# Ham-Dip-V2-002.net
KiCad netlist of a schematic drawn in EAGLE
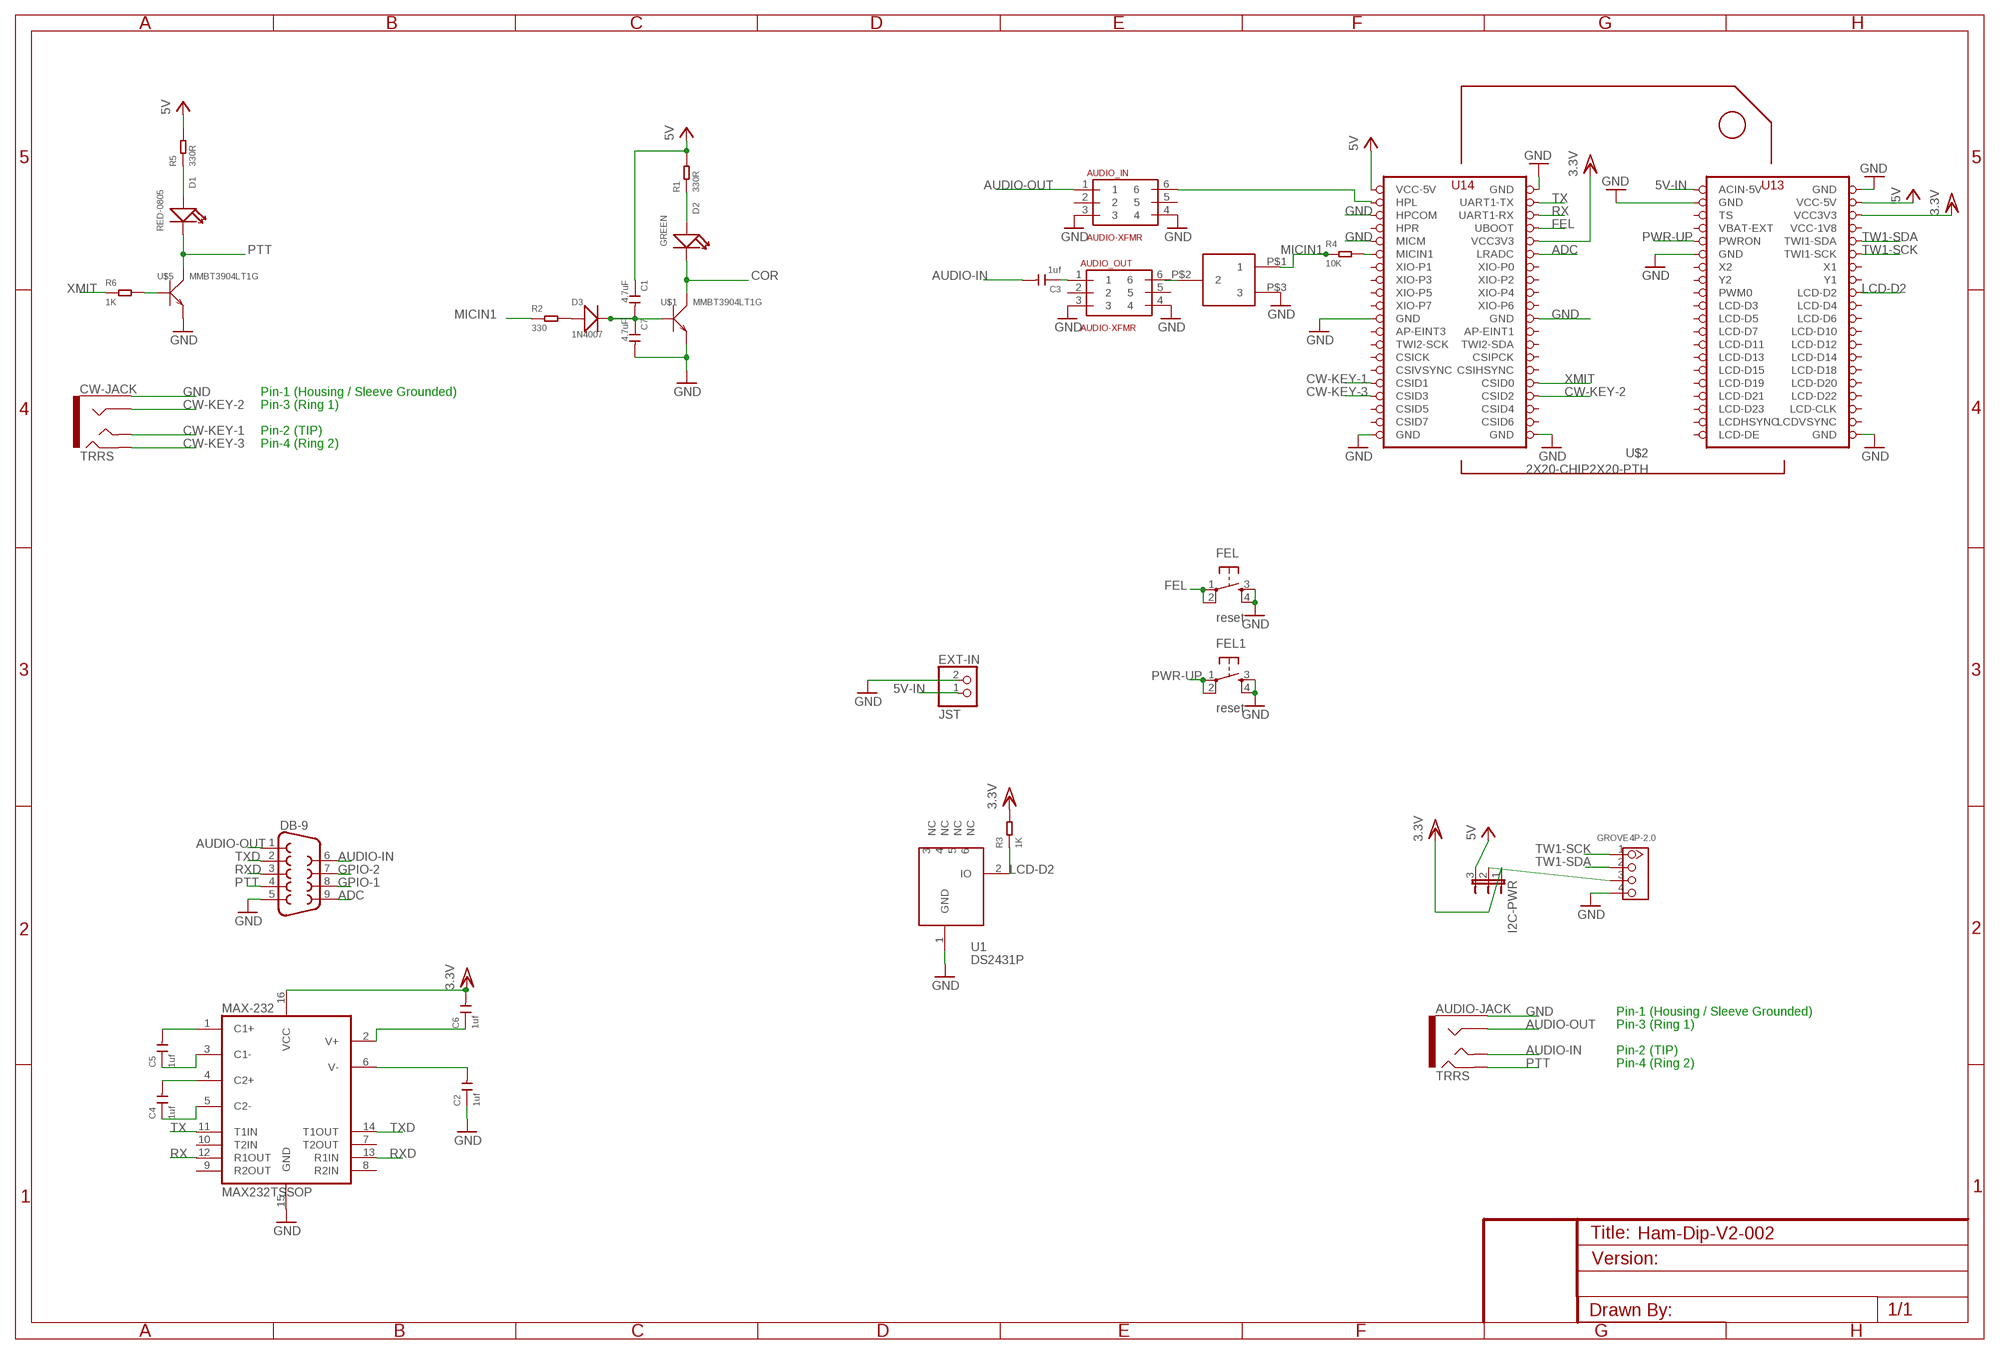
[diagram p0: schematic, sheet 1]

(export (version "E")
  (design (tool "Eeschema 10.0.6"))
  (components
    (comp (ref "AUDIO-JACK")
      (value "TRRS")
      (footprint "eagle-import:AUDIO-JACK-TRRS-SMD")
      (libsource (lib "eagle-import") (part "AUDIO-JACK3"))
    )
    (comp (ref "AUDIO_IN")
      (value "AUDIO-XFMR")
      (footprint "eagle-import:SM-LP-5001")
      (libsource (lib "eagle-import") (part "SM-LP-5001"))
    )
    (comp (ref "AUDIO_OUT")
      (value "AUDIO-XFMR")
      (footprint "eagle-import:SM-LP-5001")
      (libsource (lib "eagle-import") (part "SM-LP-5001"))
    )
    (comp (ref "C1")
      (value "4.7uF")
      (footprint "eagle-import:C0805")
      (fields (field (name "MPN") "CC0805KKX7R8BB105"))
      (libsource (lib "eagle-import") (part "CERAMIC-1UF-25V-10%-X7R(0805)"))
    )
    (comp (ref "C2")
      (value "1uf")
      (footprint "eagle-import:C0805")
      (fields (field (name "MPN") "CC0805KKX7R8BB105"))
      (libsource (lib "eagle-import") (part "CERAMIC-1UF-25V-10%-X7R(0805)"))
    )
    (comp (ref "C3")
      (value "1uf")
      (footprint "eagle-import:C0805")
      (fields (field (name "MPN") "CC0805KKX7R8BB105"))
      (libsource (lib "eagle-import") (part "CERAMIC-1UF-25V-10%-X7R(0805)"))
    )
    (comp (ref "C4")
      (value "1uf")
      (footprint "eagle-import:C0805")
      (fields (field (name "MPN") "CC0805KKX7R8BB105"))
      (libsource (lib "eagle-import") (part "CERAMIC-1UF-25V-10%-X7R(0805)"))
    )
    (comp (ref "C5")
      (value "1uf")
      (footprint "eagle-import:C0805")
      (fields (field (name "MPN") "CC0805KKX7R8BB105"))
      (libsource (lib "eagle-import") (part "CERAMIC-1UF-25V-10%-X7R(0805)"))
    )
    (comp (ref "C6")
      (value "1uf")
      (footprint "eagle-import:C0805")
      (fields (field (name "MPN") "CC0805KKX7R8BB105"))
      (libsource (lib "eagle-import") (part "CERAMIC-1UF-25V-10%-X7R(0805)"))
    )
    (comp (ref "C7")
      (value "4.7uF")
      (footprint "eagle-import:C0805")
      (fields (field (name "MPN") "CC0805KKX7R8BB105"))
      (libsource (lib "eagle-import") (part "CERAMIC-1UF-25V-10%-X7R(0805)"))
    )
    (comp (ref "CW-JACK")
      (value "TRRS")
      (footprint "eagle-import:AUDIO-JACK-TRRS-SMD")
      (libsource (lib "eagle-import") (part "AUDIO-JACK3"))
    )
    (comp (ref "D1")
      (value "RED-0805")
      (footprint "eagle-import:LED-0805")
      (fields (field (name "MPN") "17-215SURC/S530-A2/TR8"))
      (libsource (lib "eagle-import") (part "SMD-LED-CLEAR-RED(0805)"))
    )
    (comp (ref "D2")
      (value "GREEN")
      (footprint "eagle-import:LED-0805")
      (fields (field (name "MPN") "17-215SURC/S530-A2/TR8"))
      (libsource (lib "eagle-import") (part "SMD-LED-CLEAR-RED(0805)"))
    )
    (comp (ref "D3")
      (value "1N4007")
      (footprint "eagle-import:DO-214AC")
      (libsource (lib "eagle-import") (part "DIODE-GEN-PURPOSE-1KV-1A(DO-214AC)"))
    )
    (comp (ref "DB-9")
      (value "DB9FEMALE")
      (footprint "eagle-import:DB9")
      (libsource (lib "eagle-import") (part "DB9FEMALE"))
    )
    (comp (ref "EXT-IN")
      (value "JST")
      (footprint "eagle-import:JST-PH-2-THM")
      (libsource (lib "eagle-import") (part "JST_2PIN-THM"))
    )
    (comp (ref "FEL")
      (value "reset")
      (footprint "eagle-import:TACTILE_SWITCH_SMD")
      (libsource (lib "eagle-import") (part "TAC_SWITCHSMD"))
    )
    (comp (ref "FEL1")
      (value "reset")
      (footprint "eagle-import:TACTILE_SWITCH_SMD")
      (libsource (lib "eagle-import") (part "TAC_SWITCHSMD"))
    )
    (comp (ref "GROVE")
      (value "4P-2.0")
      (footprint "eagle-import:HW4-2.0")
      (libsource (lib "eagle-import") (part "GROVE-CONNECTOR-DIP(4P-2.0)"))
    )
    (comp (ref "I2C-PWR")
      (value "JP2E")
      (footprint "eagle-import:JP2")
      (libsource (lib "eagle-import") (part "JP2E"))
    )
    (comp (ref "MAX-232")
      (value "MAX232TSSOP")
      (footprint "eagle-import:TSSOP16")
      (libsource (lib "eagle-import") (part "MAX232TSSOP"))
    )
    (comp (ref "R1")
      (value "330R")
      (footprint "eagle-import:R0805")
      (fields (field (name "MPN") "RC0805JR-07220RL"))
      (libsource (lib "eagle-import") (part "SMD-RES-220R-5%-1/8W(0805)"))
    )
    (comp (ref "R2")
      (value "330")
      (footprint "eagle-import:R0805")
      (fields (field (name "MPN") "RC0805JR-07220RL"))
      (libsource (lib "eagle-import") (part "SMD-RES-220R-5%-1/8W(0805)"))
    )
    (comp (ref "R3")
      (value "1K")
      (footprint "eagle-import:R0805")
      (fields (field (name "MPN") "RC0805JR-07220RL"))
      (libsource (lib "eagle-import") (part "SMD-RES-220R-5%-1/8W(0805)"))
    )
    (comp (ref "R4")
      (value "10K")
      (footprint "eagle-import:R0805")
      (fields (field (name "MPN") "RC0805FR-0710KL"))
      (libsource (lib "eagle-import") (part "SMD-RES-10K-1%-1/8W(0805)"))
    )
    (comp (ref "R5")
      (value "330R")
      (footprint "eagle-import:R0805")
      (fields (field (name "MPN") "RC0805JR-07220RL"))
      (libsource (lib "eagle-import") (part "SMD-RES-220R-5%-1/8W(0805)"))
    )
    (comp (ref "R6")
      (value "1K")
      (footprint "eagle-import:R0805")
      (fields (field (name "MPN") "RC0805JR-07220RL"))
      (libsource (lib "eagle-import") (part "SMD-RES-220R-5%-1/8W(0805)"))
    )
    (comp (ref "U$1")
      (value "MMBT3904LT1G")
      (footprint "eagle-import:SOT-23")
      (libsource (lib "eagle-import") (part "SMD-TRANSISTORS-NPN-40V-200MA-MMBT3904LT1G(SOT-23)"))
    )
    (comp (ref "U$2")
      (value "2X20-CHIP2X20-PTH")
      (footprint "eagle-import:2X20CHIP-TH")
      (fields (field (name "VENDOR_PART_NUMBER") "AWHW40-G-SMD-R (single)"))
      (libsource (lib "eagle-import") (part "2X20-CHIP2X20-PTH-CHIP_A"))
    )
    (comp (ref "U$3")
      (value "TC33X")
      (footprint "eagle-import:TC33X")
      (libsource (lib "eagle-import") (part "TC33X"))
    )
    (comp (ref "U$5")
      (value "MMBT3904LT1G")
      (footprint "eagle-import:SOT-23")
      (libsource (lib "eagle-import") (part "SMD-TRANSISTORS-NPN-40V-200MA-MMBT3904LT1G(SOT-23)"))
    )
    (comp (ref "U1")
      (value "DS2431P")
      (footprint "eagle-import:TSOC6")
      (fields (field (name "MFG") "DIGIKEY") (field (name "VENDOR_PART_NUMBER") "DS2431P+T&R"))
      (libsource (lib "eagle-import") (part "DS2431P"))
    )
  )
  (nets
    (net (code "1") (name "/5V-IN") (class "Default")
      (node (ref "EXT-IN") (pin "1") (pinfunction "2_1") (pintype "passive"))
      (node (ref "U$2") (pin "CHG-IN") (pinfunction "ACIN-5V_CHG-IN") (pintype "passive"))
    )
    (net (code "2") (name "/ADC") (class "Default")
      (node (ref "DB-9") (pin "9") (pinfunction "9_9") (pintype "passive"))
      (node (ref "U$2") (pin "LRADC") (pinfunction "LRADC_LRADC") (pintype "passive"))
    )
    (net (code "3") (name "/AUDIO-IN") (class "Default")
      (node (ref "AUDIO-JACK") (pin "TIP") (pinfunction "TIP_TIP") (pintype "bidirectional"))
      (node (ref "C3") (pin "2") (pinfunction "2_2") (pintype "passive"))
      (node (ref "DB-9") (pin "6") (pinfunction "6_6") (pintype "passive"))
    )
    (net (code "4") (name "/AUDIO-OUT") (class "Default")
      (node (ref "AUDIO-JACK") (pin "RING1") (pinfunction "RING1_RING1") (pintype "bidirectional"))
      (node (ref "AUDIO_IN") (pin "1") (pinfunction "1_1") (pintype "bidirectional"))
      (node (ref "DB-9") (pin "1") (pinfunction "1_1") (pintype "passive"))
    )
    (net (code "5") (name "/COR") (class "Default")
      (node (ref "D2") (pin "-") (pinfunction "-_-") (pintype "passive"))
      (node (ref "U$1") (pin "3") (pinfunction "C_3") (pintype "passive"))
    )
    (net (code "6") (name "/CW-KEY-1") (class "Default")
      (node (ref "CW-JACK") (pin "TIP") (pinfunction "TIP_TIP") (pintype "bidirectional"))
      (node (ref "U$2") (pin "CSID1") (pinfunction "CSID1_CSID1") (pintype "passive"))
    )
    (net (code "7") (name "/CW-KEY-2") (class "Default")
      (node (ref "CW-JACK") (pin "RING1") (pinfunction "RING1_RING1") (pintype "bidirectional"))
      (node (ref "U$2") (pin "CSID2") (pinfunction "CSID2_CSID2") (pintype "passive"))
    )
    (net (code "8") (name "/CW-KEY-3") (class "Default")
      (node (ref "CW-JACK") (pin "RING2") (pinfunction "RING2_RING2") (pintype "bidirectional"))
      (node (ref "U$2") (pin "CSID3") (pinfunction "CSID3_CSID3") (pintype "passive"))
    )
    (net (code "9") (name "/FEL") (class "Default")
      (node (ref "FEL") (pin "1") (pinfunction "1_1") (pintype "passive"))
      (node (ref "FEL") (pin "2") (pinfunction "2_2") (pintype "passive"))
      (node (ref "U$2") (pin "FEL") (pinfunction "UBOOT_FEL") (pintype "passive"))
    )
    (net (code "10") (name "/GPIO-1") (class "Default")
      (node (ref "DB-9") (pin "8") (pinfunction "8_8") (pintype "passive"))
    )
    (net (code "11") (name "/GPIO-2") (class "Default")
      (node (ref "DB-9") (pin "7") (pinfunction "7_7") (pintype "passive"))
    )
    (net (code "12") (name "/LCD-D2") (class "Default")
      (node (ref "R3") (pin "1") (pinfunction "1_1") (pintype "passive"))
      (node (ref "U$2") (pin "LCD-D2") (pinfunction "LCD-D2_LCD-D2") (pintype "passive"))
      (node (ref "U1") (pin "2") (pinfunction "IO_2") (pintype "bidirectional"))
    )
    (net (code "13") (name "/MICIN1") (class "Default")
      (node (ref "R2") (pin "1") (pinfunction "1_1") (pintype "passive"))
      (node (ref "R4") (pin "2") (pinfunction "2_2") (pintype "passive"))
      (node (ref "U$2") (pin "MICIN1") (pinfunction "MICIN1_MICIN1") (pintype "passive"))
    )
    (net (code "14") (name "/PTT") (class "Default")
      (node (ref "AUDIO-JACK") (pin "RING2") (pinfunction "RING2_RING2") (pintype "bidirectional"))
      (node (ref "D1") (pin "-") (pinfunction "-_-") (pintype "passive"))
      (node (ref "DB-9") (pin "4") (pinfunction "4_4") (pintype "passive"))
      (node (ref "U$5") (pin "3") (pinfunction "C_3") (pintype "passive"))
    )
    (net (code "15") (name "/PWR-UP") (class "Default")
      (node (ref "FEL1") (pin "1") (pinfunction "1_1") (pintype "passive"))
      (node (ref "FEL1") (pin "2") (pinfunction "2_2") (pintype "passive"))
      (node (ref "U$2") (pin "PWRON") (pinfunction "PWRON_PWRON") (pintype "passive"))
    )
    (net (code "16") (name "/RX") (class "Default")
      (node (ref "MAX-232") (pin "12") (pinfunction "R1OUT_12") (pintype "output"))
      (node (ref "U$2") (pin "UART1-RX") (pinfunction "UART1-RX_UART1-RX") (pintype "passive"))
    )
    (net (code "17") (name "/RXD") (class "Default")
      (node (ref "DB-9") (pin "3") (pinfunction "3_3") (pintype "passive"))
      (node (ref "MAX-232") (pin "13") (pinfunction "R1IN_13") (pintype "input"))
    )
    (net (code "18") (name "/TW1-SCK") (class "Default")
      (node (ref "GROVE") (pin "1") (pinfunction "1_1") (pintype "bidirectional"))
      (node (ref "U$2") (pin "TWI1-SCK") (pinfunction "TWI1-SCK_TWI1-SCK") (pintype "passive"))
    )
    (net (code "19") (name "/TW1-SDA") (class "Default")
      (node (ref "GROVE") (pin "2") (pinfunction "2_2") (pintype "bidirectional"))
      (node (ref "U$2") (pin "TWI1-SDA") (pinfunction "TWI1-SDA_TWI1-SDA") (pintype "passive"))
    )
    (net (code "20") (name "/TX") (class "Default")
      (node (ref "MAX-232") (pin "11") (pinfunction "T1IN_11") (pintype "input"))
      (node (ref "U$2") (pin "UART1-TX") (pinfunction "UART1-TX_UART1-TX") (pintype "passive"))
    )
    (net (code "21") (name "/TXD") (class "Default")
      (node (ref "DB-9") (pin "2") (pinfunction "2_2") (pintype "passive"))
      (node (ref "MAX-232") (pin "14") (pinfunction "T1OUT_14") (pintype "output"))
    )
    (net (code "22") (name "/VCC-1V8") (class "Default")
      (node (ref "U$2") (pin "VCC1V8") (pinfunction "VCC-1V8_VCC1V8") (pintype "power_in"))
    )
    (net (code "23") (name "/XMIT") (class "Default")
      (node (ref "R6") (pin "1") (pinfunction "1_1") (pintype "passive"))
      (node (ref "U$2") (pin "CSID0") (pinfunction "CSID0_CSID0") (pintype "passive"))
    )
    (net (code "24") (name "3.3V") (class "Default")
      (node (ref "C6") (pin "2") (pinfunction "2_2") (pintype "passive"))
      (node (ref "I2C-PWR") (pin "1") (pinfunction "1_1") (pintype "passive"))
      (node (ref "MAX-232") (pin "16") (pinfunction "VCC_16") (pintype "bidirectional"))
      (node (ref "R3") (pin "2") (pinfunction "2_2") (pintype "passive"))
      (node (ref "U$2") (pin "VCC3V3") (pinfunction "VCC3V3_VCC3V3") (pintype "power_in"))
      (node (ref "U$2") (pin "VCC3V3@1") (pinfunction "VCC3V3_VCC3V3@1") (pintype "power_in"))
    )
    (net (code "25") (name "5V") (class "Default")
      (node (ref "C1") (pin "1") (pinfunction "1_1") (pintype "passive"))
      (node (ref "I2C-PWR") (pin "3") (pinfunction "3_3") (pintype "passive"))
      (node (ref "R1") (pin "2") (pinfunction "2_2") (pintype "passive"))
      (node (ref "R5") (pin "2") (pinfunction "2_2") (pintype "passive"))
      (node (ref "U$2") (pin "VCC5V@0") (pinfunction "VCC-5V_VCC5V@0") (pintype "power_in"))
      (node (ref "U$2") (pin "VCC5V@1") (pinfunction "VCC-5V_VCC5V@1") (pintype "power_in"))
    )
    (net (code "26") (name "GND") (class "Default")
      (node (ref "AUDIO-JACK") (pin "EARTH") (pinfunction "EARTH_EARTH") (pintype "bidirectional"))
      (node (ref "AUDIO_IN") (pin "3") (pinfunction "3_3") (pintype "bidirectional"))
      (node (ref "AUDIO_IN") (pin "4") (pinfunction "4_4") (pintype "bidirectional"))
      (node (ref "AUDIO_OUT") (pin "3") (pinfunction "3_3") (pintype "bidirectional"))
      (node (ref "AUDIO_OUT") (pin "4") (pinfunction "4_4") (pintype "bidirectional"))
      (node (ref "C2") (pin "1") (pinfunction "1_1") (pintype "passive"))
      (node (ref "C7") (pin "2") (pinfunction "2_2") (pintype "passive"))
      (node (ref "CW-JACK") (pin "EARTH") (pinfunction "EARTH_EARTH") (pintype "bidirectional"))
      (node (ref "DB-9") (pin "5") (pinfunction "5_5") (pintype "passive"))
      (node (ref "EXT-IN") (pin "2") (pinfunction "1_2") (pintype "passive"))
      (node (ref "FEL") (pin "3") (pinfunction "3_3") (pintype "passive"))
      (node (ref "FEL") (pin "4") (pinfunction "4_4") (pintype "passive"))
      (node (ref "FEL1") (pin "3") (pinfunction "3_3") (pintype "passive"))
      (node (ref "FEL1") (pin "4") (pinfunction "4_4") (pintype "passive"))
      (node (ref "GROVE") (pin "4") (pinfunction "4_4") (pintype "bidirectional"))
      (node (ref "MAX-232") (pin "15") (pinfunction "GND_15") (pintype "bidirectional"))
      (node (ref "U$1") (pin "2") (pinfunction "E_2") (pintype "passive"))
      (node (ref "U$2") (pin "GND@1") (pinfunction "GND_GND@1") (pintype "power_in"))
      (node (ref "U$2") (pin "GND@10") (pinfunction "GND_GND@10") (pintype "power_in"))
      (node (ref "U$2") (pin "GND@2") (pinfunction "GND_GND@2") (pintype "power_in"))
      (node (ref "U$2") (pin "GND@3") (pinfunction "GND_GND@3") (pintype "power_in"))
      (node (ref "U$2") (pin "GND@4") (pinfunction "GND_GND@4") (pintype "power_in"))
      (node (ref "U$2") (pin "GND@5") (pinfunction "GND_GND@5") (pintype "power_in"))
      (node (ref "U$2") (pin "GND@6") (pinfunction "GND_GND@6") (pintype "power_in"))
      (node (ref "U$2") (pin "GND@7") (pinfunction "GND_GND@7") (pintype "power_in"))
      (node (ref "U$2") (pin "GND@8") (pinfunction "GND_GND@8") (pintype "power_in"))
      (node (ref "U$2") (pin "HPCOM") (pinfunction "HPCOM_HPCOM") (pintype "passive"))
      (node (ref "U$2") (pin "MICM") (pinfunction "MICM_MICM") (pintype "passive"))
      (node (ref "U$3") (pin "P$3") (pinfunction "3_P$3") (pintype "bidirectional"))
      (node (ref "U$5") (pin "2") (pinfunction "E_2") (pintype "passive"))
      (node (ref "U1") (pin "1") (pinfunction "GND_1") (pintype "bidirectional"))
    )
    (net (code "27") (name "Net-(AUDIO_IN-Pad6)") (class "Default")
      (node (ref "AUDIO_IN") (pin "6") (pinfunction "6_6") (pintype "bidirectional"))
      (node (ref "U$2") (pin "HPL") (pinfunction "HPL_HPL") (pintype "passive"))
    )
    (net (code "28") (name "Net-(AUDIO_OUT-Pad1)") (class "Default")
      (node (ref "AUDIO_OUT") (pin "1") (pinfunction "1_1") (pintype "bidirectional"))
      (node (ref "C3") (pin "1") (pinfunction "1_1") (pintype "passive"))
    )
    (net (code "29") (name "Net-(D1-Pad+)") (class "Default")
      (node (ref "D1") (pin "+") (pinfunction "+_+") (pintype "passive"))
      (node (ref "R5") (pin "1") (pinfunction "1_1") (pintype "passive"))
    )
    (net (code "30") (name "Net-(D2-Pad+)") (class "Default")
      (node (ref "D2") (pin "+") (pinfunction "+_+") (pintype "passive"))
      (node (ref "R1") (pin "1") (pinfunction "1_1") (pintype "passive"))
    )
    (net (code "31") (name "Net-(D3-+)") (class "Default")
      (node (ref "D3") (pin "1") (pinfunction "+_1") (pintype "passive"))
      (node (ref "R2") (pin "2") (pinfunction "2_2") (pintype "passive"))
    )
    (net (code "32") (name "Net-(D3--)") (class "Default")
      (node (ref "C1") (pin "2") (pinfunction "2_2") (pintype "passive"))
      (node (ref "C7") (pin "1") (pinfunction "1_1") (pintype "passive"))
      (node (ref "D3") (pin "2") (pinfunction "-_2") (pintype "passive"))
      (node (ref "U$1") (pin "1") (pinfunction "B_1") (pintype "passive"))
    )
    (net (code "33") (name "Net-(GROVE-Pad3)") (class "Default")
      (node (ref "GROVE") (pin "3") (pinfunction "3_3") (pintype "bidirectional"))
      (node (ref "I2C-PWR") (pin "2") (pinfunction "2_2") (pintype "passive"))
    )
    (net (code "34") (name "Net-(MAX-232-C1+)") (class "Default")
      (node (ref "C5") (pin "2") (pinfunction "2_2") (pintype "passive"))
      (node (ref "MAX-232") (pin "1") (pinfunction "C1+_1") (pintype "bidirectional"))
    )
    (net (code "35") (name "Net-(MAX-232-C1-)") (class "Default")
      (node (ref "C5") (pin "1") (pinfunction "1_1") (pintype "passive"))
      (node (ref "MAX-232") (pin "3") (pinfunction "C1-_3") (pintype "bidirectional"))
    )
    (net (code "36") (name "Net-(MAX-232-C2+)") (class "Default")
      (node (ref "C4") (pin "2") (pinfunction "2_2") (pintype "passive"))
      (node (ref "MAX-232") (pin "4") (pinfunction "C2+_4") (pintype "bidirectional"))
    )
    (net (code "37") (name "Net-(MAX-232-C2-)") (class "Default")
      (node (ref "C4") (pin "1") (pinfunction "1_1") (pintype "passive"))
      (node (ref "MAX-232") (pin "5") (pinfunction "C2-_5") (pintype "bidirectional"))
    )
    (net (code "38") (name "Net-(MAX-232-V+)") (class "Default")
      (node (ref "C6") (pin "1") (pinfunction "1_1") (pintype "passive"))
      (node (ref "MAX-232") (pin "2") (pinfunction "V+_2") (pintype "bidirectional"))
    )
    (net (code "39") (name "Net-(MAX-232-V-)") (class "Default")
      (node (ref "C2") (pin "2") (pinfunction "2_2") (pintype "passive"))
      (node (ref "MAX-232") (pin "6") (pinfunction "V-_6") (pintype "bidirectional"))
    )
    (net (code "40") (name "Net-(U$3-1)") (class "Default")
      (node (ref "R4") (pin "1") (pinfunction "1_1") (pintype "passive"))
      (node (ref "U$3") (pin "P$1") (pinfunction "1_P$1") (pintype "bidirectional"))
    )
    (net (code "41") (name "Net-(U$5-B)") (class "Default")
      (node (ref "R6") (pin "2") (pinfunction "2_2") (pintype "passive"))
      (node (ref "U$5") (pin "1") (pinfunction "B_1") (pintype "passive"))
    )
    (net (code "42") (name "unconnected-(AUDIO_IN-Pad2)") (class "Default")
      (node (ref "AUDIO_IN") (pin "2") (pinfunction "2_2") (pintype "bidirectional"))
    )
    (net (code "43") (name "unconnected-(AUDIO_IN-Pad5)") (class "Default")
      (node (ref "AUDIO_IN") (pin "5") (pinfunction "5_5") (pintype "bidirectional"))
    )
    (net (code "44") (name "unconnected-(AUDIO_OUT-Pad2)") (class "Default")
      (node (ref "AUDIO_OUT") (pin "2") (pinfunction "2_2") (pintype "bidirectional"))
    )
    (net (code "45") (name "unconnected-(AUDIO_OUT-Pad5)") (class "Default")
      (node (ref "AUDIO_OUT") (pin "5") (pinfunction "5_5") (pintype "bidirectional"))
    )
    (net (code "46") (name "unconnected-(AUDIO_OUT-Pad6)") (class "Default")
      (node (ref "AUDIO_OUT") (pin "6") (pinfunction "6_6") (pintype "bidirectional"))
    )
    (net (code "47") (name "unconnected-(MAX-232-R2IN-Pad8)") (class "Default")
      (node (ref "MAX-232") (pin "8") (pinfunction "R2IN_8") (pintype "input"))
    )
    (net (code "48") (name "unconnected-(MAX-232-R2OUT-Pad9)") (class "Default")
      (node (ref "MAX-232") (pin "9") (pinfunction "R2OUT_9") (pintype "output"))
    )
    (net (code "49") (name "unconnected-(MAX-232-T2IN-Pad10)") (class "Default")
      (node (ref "MAX-232") (pin "10") (pinfunction "T2IN_10") (pintype "input"))
    )
    (net (code "50") (name "unconnected-(MAX-232-T2OUT-Pad7)") (class "Default")
      (node (ref "MAX-232") (pin "7") (pinfunction "T2OUT_7") (pintype "output"))
    )
    (net (code "51") (name "unconnected-(U$2-LCDHSYNC-PadLCD-HSYNC)") (class "Default")
      (node (ref "U$2") (pin "LCD-HSYNC") (pinfunction "LCDHSYNC_LCD-HSYNC") (pintype "passive"))
    )
    (net (code "52") (name "unconnected-(U$2-LCDVSYNC-PadLCD-VSYNC)") (class "Default")
      (node (ref "U$2") (pin "LCD-VSYNC") (pinfunction "LCDVSYNC_LCD-VSYNC") (pintype "passive"))
    )
    (net (code "53") (name "unconnected-(U$2-PadAP-EINT1)") (class "Default")
      (node (ref "U$2") (pin "AP-EINT1") (pinfunction "AP-EINT1_AP-EINT1") (pintype "passive"))
    )
    (net (code "54") (name "unconnected-(U$2-PadAP-EINT3)") (class "Default")
      (node (ref "U$2") (pin "AP-EINT3") (pinfunction "AP-EINT3_AP-EINT3") (pintype "passive"))
    )
    (net (code "55") (name "unconnected-(U$2-PadCSICK)") (class "Default")
      (node (ref "U$2") (pin "CSICK") (pinfunction "CSICK_CSICK") (pintype "passive"))
    )
    (net (code "56") (name "unconnected-(U$2-PadCSID4)") (class "Default")
      (node (ref "U$2") (pin "CSID4") (pinfunction "CSID4_CSID4") (pintype "passive"))
    )
    (net (code "57") (name "unconnected-(U$2-PadCSID5)") (class "Default")
      (node (ref "U$2") (pin "CSID5") (pinfunction "CSID5_CSID5") (pintype "passive"))
    )
    (net (code "58") (name "unconnected-(U$2-PadCSID6)") (class "Default")
      (node (ref "U$2") (pin "CSID6") (pinfunction "CSID6_CSID6") (pintype "passive"))
    )
    (net (code "59") (name "unconnected-(U$2-PadCSID7)") (class "Default")
      (node (ref "U$2") (pin "CSID7") (pinfunction "CSID7_CSID7") (pintype "passive"))
    )
    (net (code "60") (name "unconnected-(U$2-PadCSIHSYNC)") (class "Default")
      (node (ref "U$2") (pin "CSIHSYNC") (pinfunction "CSIHSYNC_CSIHSYNC") (pintype "passive"))
    )
    (net (code "61") (name "unconnected-(U$2-PadCSIPCK)") (class "Default")
      (node (ref "U$2") (pin "CSIPCK") (pinfunction "CSIPCK_CSIPCK") (pintype "passive"))
    )
    (net (code "62") (name "unconnected-(U$2-PadCSIVSYNC)") (class "Default")
      (node (ref "U$2") (pin "CSIVSYNC") (pinfunction "CSIVSYNC_CSIVSYNC") (pintype "passive"))
    )
    (net (code "63") (name "unconnected-(U$2-PadHPR)") (class "Default")
      (node (ref "U$2") (pin "HPR") (pinfunction "HPR_HPR") (pintype "passive"))
    )
    (net (code "64") (name "unconnected-(U$2-PadLCD-CLK)") (class "Default")
      (node (ref "U$2") (pin "LCD-CLK") (pinfunction "LCD-CLK_LCD-CLK") (pintype "passive"))
    )
    (net (code "65") (name "unconnected-(U$2-PadLCD-D3)") (class "Default")
      (node (ref "U$2") (pin "LCD-D3") (pinfunction "LCD-D3_LCD-D3") (pintype "passive"))
    )
    (net (code "66") (name "unconnected-(U$2-PadLCD-D4)") (class "Default")
      (node (ref "U$2") (pin "LCD-D4") (pinfunction "LCD-D4_LCD-D4") (pintype "passive"))
    )
    (net (code "67") (name "unconnected-(U$2-PadLCD-D5)") (class "Default")
      (node (ref "U$2") (pin "LCD-D5") (pinfunction "LCD-D5_LCD-D5") (pintype "passive"))
    )
    (net (code "68") (name "unconnected-(U$2-PadLCD-D6)") (class "Default")
      (node (ref "U$2") (pin "LCD-D6") (pinfunction "LCD-D6_LCD-D6") (pintype "passive"))
    )
    (net (code "69") (name "unconnected-(U$2-PadLCD-D7)") (class "Default")
      (node (ref "U$2") (pin "LCD-D7") (pinfunction "LCD-D7_LCD-D7") (pintype "passive"))
    )
    (net (code "70") (name "unconnected-(U$2-PadLCD-D10)") (class "Default")
      (node (ref "U$2") (pin "LCD-D10") (pinfunction "LCD-D10_LCD-D10") (pintype "passive"))
    )
    (net (code "71") (name "unconnected-(U$2-PadLCD-D11)") (class "Default")
      (node (ref "U$2") (pin "LCD-D11") (pinfunction "LCD-D11_LCD-D11") (pintype "passive"))
    )
    (net (code "72") (name "unconnected-(U$2-PadLCD-D12)") (class "Default")
      (node (ref "U$2") (pin "LCD-D12") (pinfunction "LCD-D12_LCD-D12") (pintype "passive"))
    )
    (net (code "73") (name "unconnected-(U$2-PadLCD-D13)") (class "Default")
      (node (ref "U$2") (pin "LCD-D13") (pinfunction "LCD-D13_LCD-D13") (pintype "passive"))
    )
    (net (code "74") (name "unconnected-(U$2-PadLCD-D14)") (class "Default")
      (node (ref "U$2") (pin "LCD-D14") (pinfunction "LCD-D14_LCD-D14") (pintype "passive"))
    )
    (net (code "75") (name "unconnected-(U$2-PadLCD-D15)") (class "Default")
      (node (ref "U$2") (pin "LCD-D15") (pinfunction "LCD-D15_LCD-D15") (pintype "passive"))
    )
    (net (code "76") (name "unconnected-(U$2-PadLCD-D18)") (class "Default")
      (node (ref "U$2") (pin "LCD-D18") (pinfunction "LCD-D18_LCD-D18") (pintype "passive"))
    )
    (net (code "77") (name "unconnected-(U$2-PadLCD-D19)") (class "Default")
      (node (ref "U$2") (pin "LCD-D19") (pinfunction "LCD-D19_LCD-D19") (pintype "passive"))
    )
    (net (code "78") (name "unconnected-(U$2-PadLCD-D20)") (class "Default")
      (node (ref "U$2") (pin "LCD-D20") (pinfunction "LCD-D20_LCD-D20") (pintype "passive"))
    )
    (net (code "79") (name "unconnected-(U$2-PadLCD-D21)") (class "Default")
      (node (ref "U$2") (pin "LCD-D21") (pinfunction "LCD-D21_LCD-D21") (pintype "passive"))
    )
    (net (code "80") (name "unconnected-(U$2-PadLCD-D22)") (class "Default")
      (node (ref "U$2") (pin "LCD-D22") (pinfunction "LCD-D22_LCD-D22") (pintype "passive"))
    )
    (net (code "81") (name "unconnected-(U$2-PadLCD-D23)") (class "Default")
      (node (ref "U$2") (pin "LCD-D23") (pinfunction "LCD-D23_LCD-D23") (pintype "passive"))
    )
    (net (code "82") (name "unconnected-(U$2-PadLCD-DE)") (class "Default")
      (node (ref "U$2") (pin "LCD-DE") (pinfunction "LCD-DE_LCD-DE") (pintype "passive"))
    )
    (net (code "83") (name "unconnected-(U$2-PadPWM0)") (class "Default")
      (node (ref "U$2") (pin "PWM0") (pinfunction "PWM0_PWM0") (pintype "passive"))
    )
    (net (code "84") (name "unconnected-(U$2-PadTS)") (class "Default")
      (node (ref "U$2") (pin "TS") (pinfunction "TS_TS") (pintype "passive"))
    )
    (net (code "85") (name "unconnected-(U$2-PadTWI2-SCK)") (class "Default")
      (node (ref "U$2") (pin "TWI2-SCK") (pinfunction "TWI2-SCK_TWI2-SCK") (pintype "passive"))
    )
    (net (code "86") (name "unconnected-(U$2-PadTWI2-SDA)") (class "Default")
      (node (ref "U$2") (pin "TWI2-SDA") (pinfunction "TWI2-SDA_TWI2-SDA") (pintype "passive"))
    )
    (net (code "87") (name "unconnected-(U$2-PadX1)") (class "Default")
      (node (ref "U$2") (pin "X1") (pinfunction "X1_X1") (pintype "passive"))
    )
    (net (code "88") (name "unconnected-(U$2-PadX2)") (class "Default")
      (node (ref "U$2") (pin "X2") (pinfunction "X2_X2") (pintype "passive"))
    )
    (net (code "89") (name "unconnected-(U$2-PadXIO-P0)") (class "Default")
      (node (ref "U$2") (pin "XIO-P0") (pinfunction "XIO-P0_XIO-P0") (pintype "passive"))
    )
    (net (code "90") (name "unconnected-(U$2-PadXIO-P1)") (class "Default")
      (node (ref "U$2") (pin "XIO-P1") (pinfunction "XIO-P1_XIO-P1") (pintype "passive"))
    )
    (net (code "91") (name "unconnected-(U$2-PadXIO-P2)") (class "Default")
      (node (ref "U$2") (pin "XIO-P2") (pinfunction "XIO-P2_XIO-P2") (pintype "passive"))
    )
    (net (code "92") (name "unconnected-(U$2-PadXIO-P3)") (class "Default")
      (node (ref "U$2") (pin "XIO-P3") (pinfunction "XIO-P3_XIO-P3") (pintype "passive"))
    )
    (net (code "93") (name "unconnected-(U$2-PadXIO-P4)") (class "Default")
      (node (ref "U$2") (pin "XIO-P4") (pinfunction "XIO-P4_XIO-P4") (pintype "passive"))
    )
    (net (code "94") (name "unconnected-(U$2-PadXIO-P5)") (class "Default")
      (node (ref "U$2") (pin "XIO-P5") (pinfunction "XIO-P5_XIO-P5") (pintype "passive"))
    )
    (net (code "95") (name "unconnected-(U$2-PadXIO-P6)") (class "Default")
      (node (ref "U$2") (pin "XIO-P6") (pinfunction "XIO-P6_XIO-P6") (pintype "passive"))
    )
    (net (code "96") (name "unconnected-(U$2-PadXIO-P7)") (class "Default")
      (node (ref "U$2") (pin "XIO-P7") (pinfunction "XIO-P7_XIO-P7") (pintype "passive"))
    )
    (net (code "97") (name "unconnected-(U$2-PadY1)") (class "Default")
      (node (ref "U$2") (pin "Y1") (pinfunction "Y1_Y1") (pintype "passive"))
    )
    (net (code "98") (name "unconnected-(U$2-PadY2)") (class "Default")
      (node (ref "U$2") (pin "Y2") (pinfunction "Y2_Y2") (pintype "passive"))
    )
    (net (code "99") (name "unconnected-(U$2-VBAT-EXT-PadBAT)") (class "Default")
      (node (ref "U$2") (pin "BAT") (pinfunction "VBAT-EXT_BAT") (pintype "passive"))
    )
    (net (code "100") (name "unconnected-(U$3-2-PadP$2)") (class "Default")
      (node (ref "U$3") (pin "P$2") (pinfunction "2_P$2") (pintype "bidirectional"))
    )
    (net (code "101") (name "unconnected-(U1-NC-Pad3)") (class "Default")
      (node (ref "U1") (pin "3") (pinfunction "NC_3") (pintype "bidirectional"))
    )
    (net (code "102") (name "unconnected-(U1-NC-Pad4)") (class "Default")
      (node (ref "U1") (pin "4") (pinfunction "NC_4") (pintype "bidirectional"))
    )
    (net (code "103") (name "unconnected-(U1-NC-Pad5)") (class "Default")
      (node (ref "U1") (pin "5") (pinfunction "NC_5") (pintype "bidirectional"))
    )
    (net (code "104") (name "unconnected-(U1-NC-Pad6)") (class "Default")
      (node (ref "U1") (pin "6") (pinfunction "NC_6") (pintype "bidirectional"))
    )
  )
)
